# headlightsV1_6.net
KiCad netlist of a schematic drawn in EAGLE
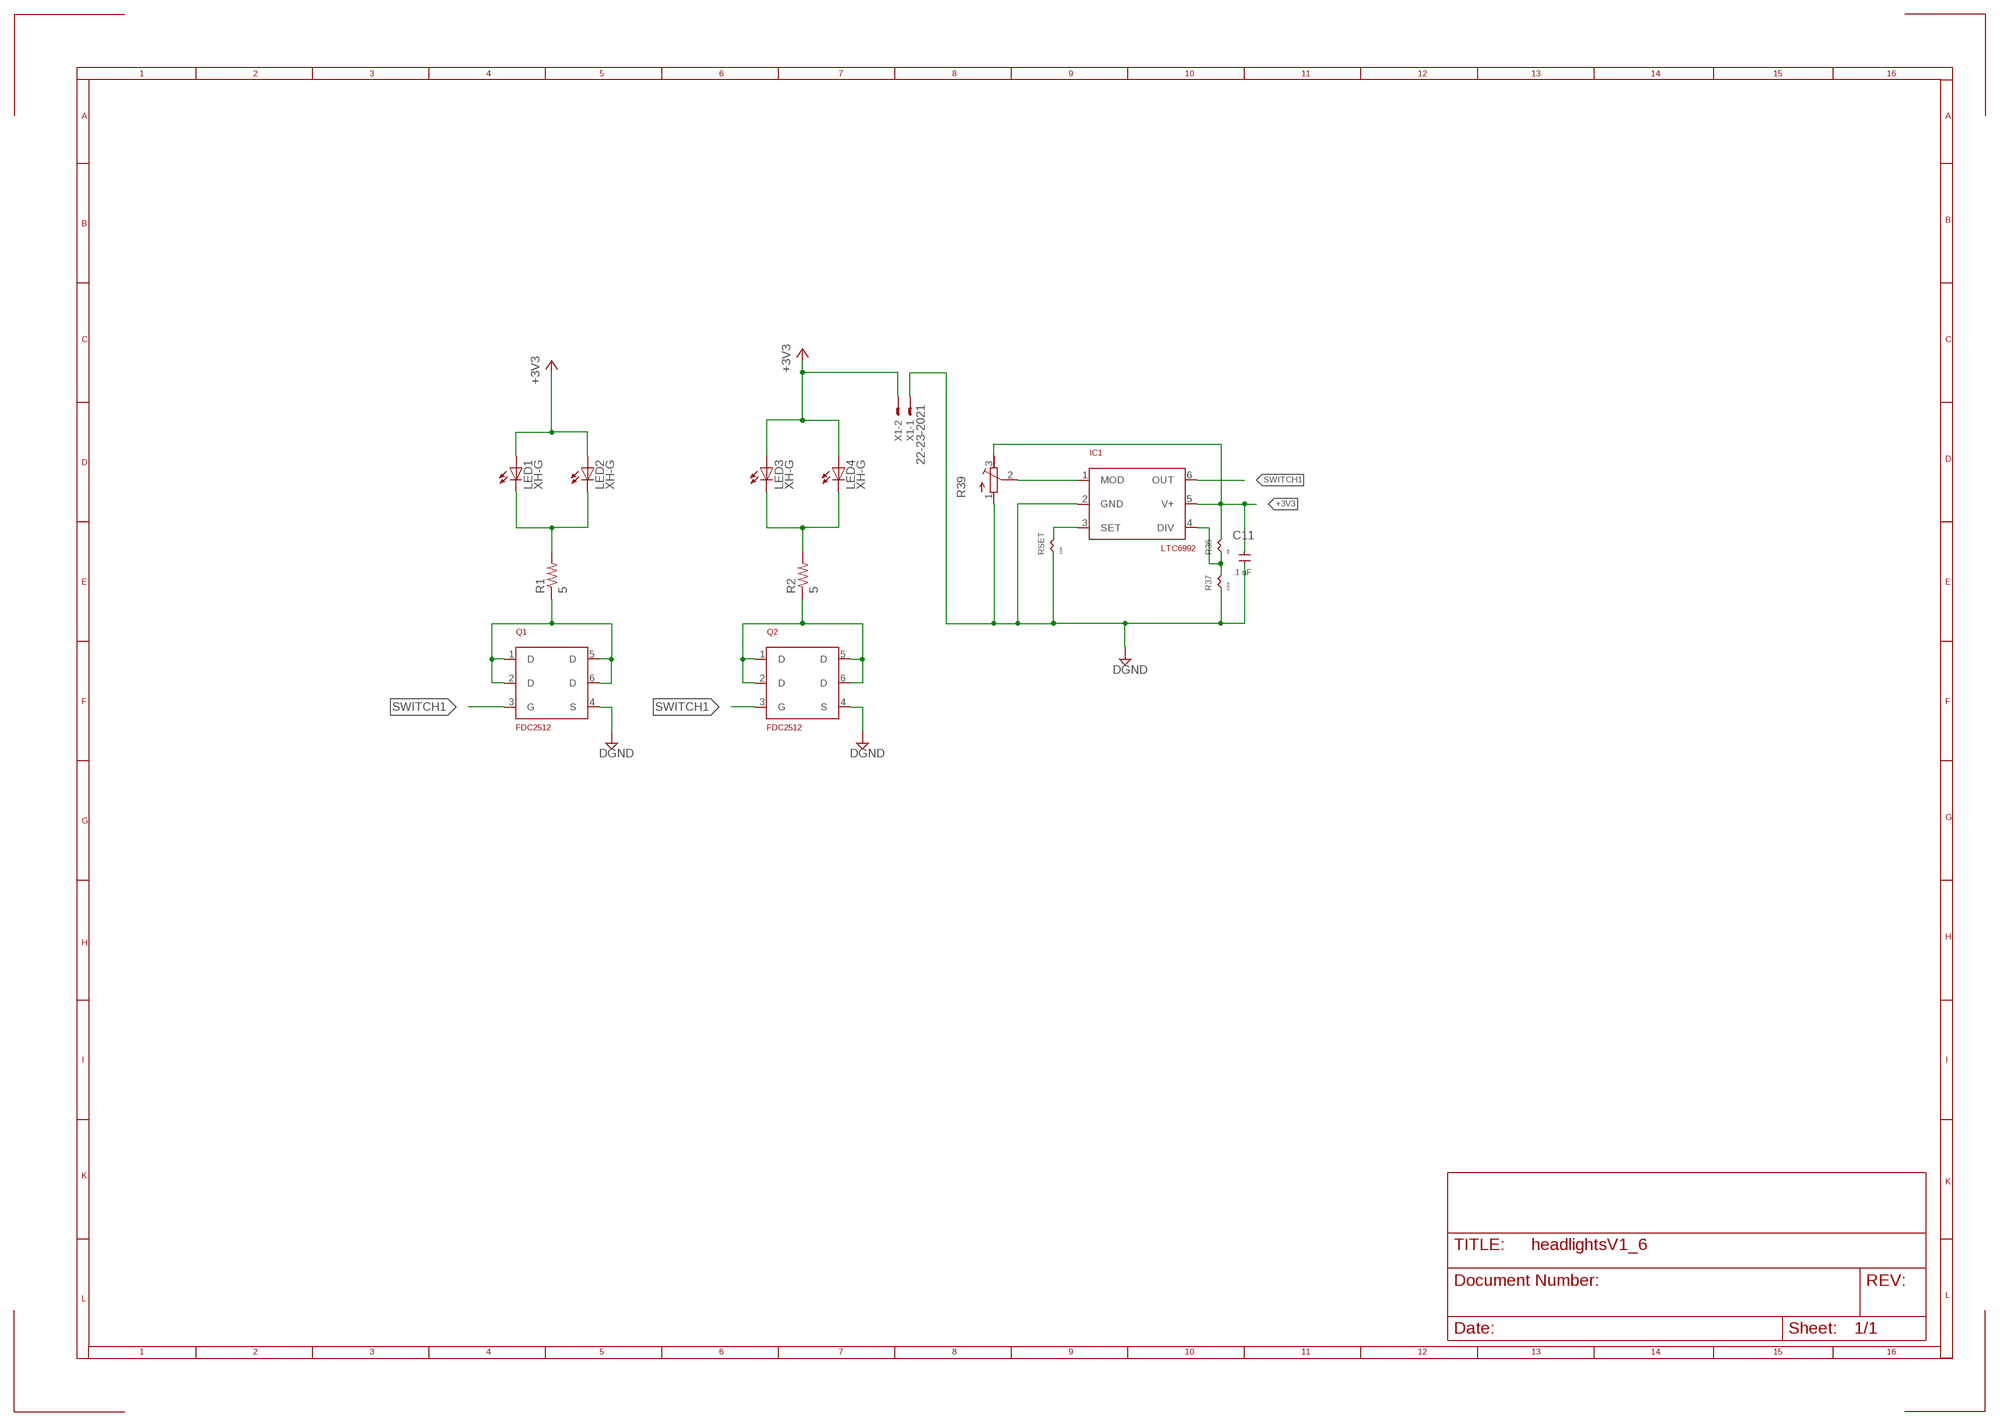
[diagram p0: schematic, sheet 1]

(export (version "E")
  (design (tool "Eeschema 10.0.6"))
  (components
    (comp (ref "C11")
      (value ".1 uF")
      (footprint "eagle-import:C0402")
      (libsource (lib "eagle-import") (part "C-ERC0402"))
    )
    (comp (ref "IC1")
      (value "LTC6992")
      (footprint "eagle-import:TSOT-23-6")
      (libsource (lib "eagle-import") (part "LTC6992"))
    )
    (comp (ref "LED1")
      (value "XH-G")
      (footprint "eagle-import:XH-G")
      (libsource (lib "eagle-import") (part "XH-G"))
    )
    (comp (ref "LED2")
      (value "XH-G")
      (footprint "eagle-import:XH-G")
      (libsource (lib "eagle-import") (part "XH-G"))
    )
    (comp (ref "LED3")
      (value "XH-G")
      (footprint "eagle-import:XH-G")
      (libsource (lib "eagle-import") (part "XH-G"))
    )
    (comp (ref "LED4")
      (value "XH-G")
      (footprint "eagle-import:XH-G")
      (libsource (lib "eagle-import") (part "XH-G"))
    )
    (comp (ref "Q1")
      (value "FDC2512")
      (footprint "eagle-import:SSOT6")
      (libsource (lib "eagle-import") (part "FDC2512"))
    )
    (comp (ref "Q2")
      (value "FDC2512")
      (footprint "eagle-import:SSOT6")
      (libsource (lib "eagle-import") (part "FDC2512"))
    )
    (comp (ref "R1")
      (value "5")
      (footprint "eagle-import:R0805")
      (libsource (lib "eagle-import") (part "R-US_R0805"))
    )
    (comp (ref "R2")
      (value "5")
      (footprint "eagle-import:R0805")
      (libsource (lib "eagle-import") (part "R-US_R0805"))
    )
    (comp (ref "R36")
      (value "10k")
      (footprint "eagle-import:R0402")
      (libsource (lib "eagle-import") (part "R-ER-TINYR402"))
    )
    (comp (ref "R37")
      (value "6.81k")
      (footprint "eagle-import:R0402")
      (libsource (lib "eagle-import") (part "R-ER-TINYR402"))
    )
    (comp (ref "R39")
      (value "R-TRIMM3304W")
      (footprint "eagle-import:RTRIM3304W")
      (libsource (lib "eagle-import") (part "R-TRIMM3304W"))
    )
    (comp (ref "RSET")
      (value "122k")
      (footprint "eagle-import:R0402")
      (libsource (lib "eagle-import") (part "R-ER-TINYR402"))
    )
    (comp (ref "X1")
      (value "22-23-2021")
      (footprint "eagle-import:22-23-2021")
      (libsource (lib "eagle-import") (part "22-23-2021"))
    )
  )
  (nets
    (net (code "1") (name "+3V3") (class "Default")
      (node (ref "C11") (pin "2") (pinfunction "P$2_2") (pintype "bidirectional"))
      (node (ref "IC1") (pin "5") (pinfunction "V+_5") (pintype "bidirectional"))
      (node (ref "LED1") (pin "2") (pinfunction "A_2") (pintype "passive"))
      (node (ref "LED2") (pin "2") (pinfunction "A_2") (pintype "passive"))
      (node (ref "LED3") (pin "2") (pinfunction "A_2") (pintype "passive"))
      (node (ref "LED4") (pin "2") (pinfunction "A_2") (pintype "passive"))
      (node (ref "R36") (pin "2") (pinfunction "P$2_2") (pintype "bidirectional"))
      (node (ref "R39") (pin "3") (pinfunction "A_3") (pintype "passive"))
      (node (ref "X1") (pin "2") (pinfunction "S_2") (pintype "passive"))
    )
    (net (code "2") (name "DGND") (class "Default")
      (node (ref "C11") (pin "1") (pinfunction "P$1_1") (pintype "bidirectional"))
      (node (ref "IC1") (pin "2") (pinfunction "GND_2") (pintype "bidirectional"))
      (node (ref "Q1") (pin "4") (pinfunction "S_4") (pintype "bidirectional"))
      (node (ref "Q2") (pin "4") (pinfunction "S_4") (pintype "bidirectional"))
      (node (ref "R37") (pin "1") (pinfunction "P$1_1") (pintype "bidirectional"))
      (node (ref "R39") (pin "1") (pinfunction "E_1") (pintype "passive"))
      (node (ref "RSET") (pin "1") (pinfunction "P$1_1") (pintype "bidirectional"))
      (node (ref "X1") (pin "1") (pinfunction "S_1") (pintype "passive"))
    )
    (net (code "3") (name "Net-(IC1-DIV)") (class "Default")
      (node (ref "IC1") (pin "4") (pinfunction "DIV_4") (pintype "bidirectional"))
      (node (ref "R36") (pin "1") (pinfunction "P$1_1") (pintype "bidirectional"))
      (node (ref "R37") (pin "2") (pinfunction "P$2_2") (pintype "bidirectional"))
    )
    (net (code "4") (name "Net-(IC1-MOD)") (class "Default")
      (node (ref "IC1") (pin "1") (pinfunction "MOD_1") (pintype "bidirectional"))
      (node (ref "R39") (pin "2") (pinfunction "S_2") (pintype "passive"))
    )
    (net (code "5") (name "Net-(IC1-SET)") (class "Default")
      (node (ref "IC1") (pin "3") (pinfunction "SET_3") (pintype "bidirectional"))
      (node (ref "RSET") (pin "2") (pinfunction "P$2_2") (pintype "bidirectional"))
    )
    (net (code "6") (name "Net-(LED1-C)") (class "Default")
      (node (ref "LED1") (pin "1") (pinfunction "C_1") (pintype "passive"))
      (node (ref "LED2") (pin "1") (pinfunction "C_1") (pintype "passive"))
      (node (ref "R1") (pin "2") (pinfunction "2_2") (pintype "passive"))
    )
    (net (code "7") (name "Net-(LED3-C)") (class "Default")
      (node (ref "LED3") (pin "1") (pinfunction "C_1") (pintype "passive"))
      (node (ref "LED4") (pin "1") (pinfunction "C_1") (pintype "passive"))
      (node (ref "R2") (pin "2") (pinfunction "2_2") (pintype "passive"))
    )
    (net (code "8") (name "Net-(Q1-D-Pad1)") (class "Default")
      (node (ref "Q1") (pin "1") (pinfunction "D_1") (pintype "bidirectional"))
      (node (ref "Q1") (pin "2") (pinfunction "D_2") (pintype "bidirectional"))
      (node (ref "Q1") (pin "5") (pinfunction "D_5") (pintype "bidirectional"))
      (node (ref "Q1") (pin "6") (pinfunction "D_6") (pintype "bidirectional"))
      (node (ref "R1") (pin "1") (pinfunction "1_1") (pintype "passive"))
    )
    (net (code "9") (name "Net-(Q2-D-Pad1)") (class "Default")
      (node (ref "Q2") (pin "1") (pinfunction "D_1") (pintype "bidirectional"))
      (node (ref "Q2") (pin "2") (pinfunction "D_2") (pintype "bidirectional"))
      (node (ref "Q2") (pin "5") (pinfunction "D_5") (pintype "bidirectional"))
      (node (ref "Q2") (pin "6") (pinfunction "D_6") (pintype "bidirectional"))
      (node (ref "R2") (pin "1") (pinfunction "1_1") (pintype "passive"))
    )
    (net (code "10") (name "SWITCH1") (class "Default")
      (node (ref "IC1") (pin "6") (pinfunction "OUT_6") (pintype "bidirectional"))
      (node (ref "Q1") (pin "3") (pinfunction "G_3") (pintype "bidirectional"))
      (node (ref "Q2") (pin "3") (pinfunction "G_3") (pintype "bidirectional"))
    )
  )
)
